# Ethernet.net
KiCad netlist of a schematic drawn in Altium Designer
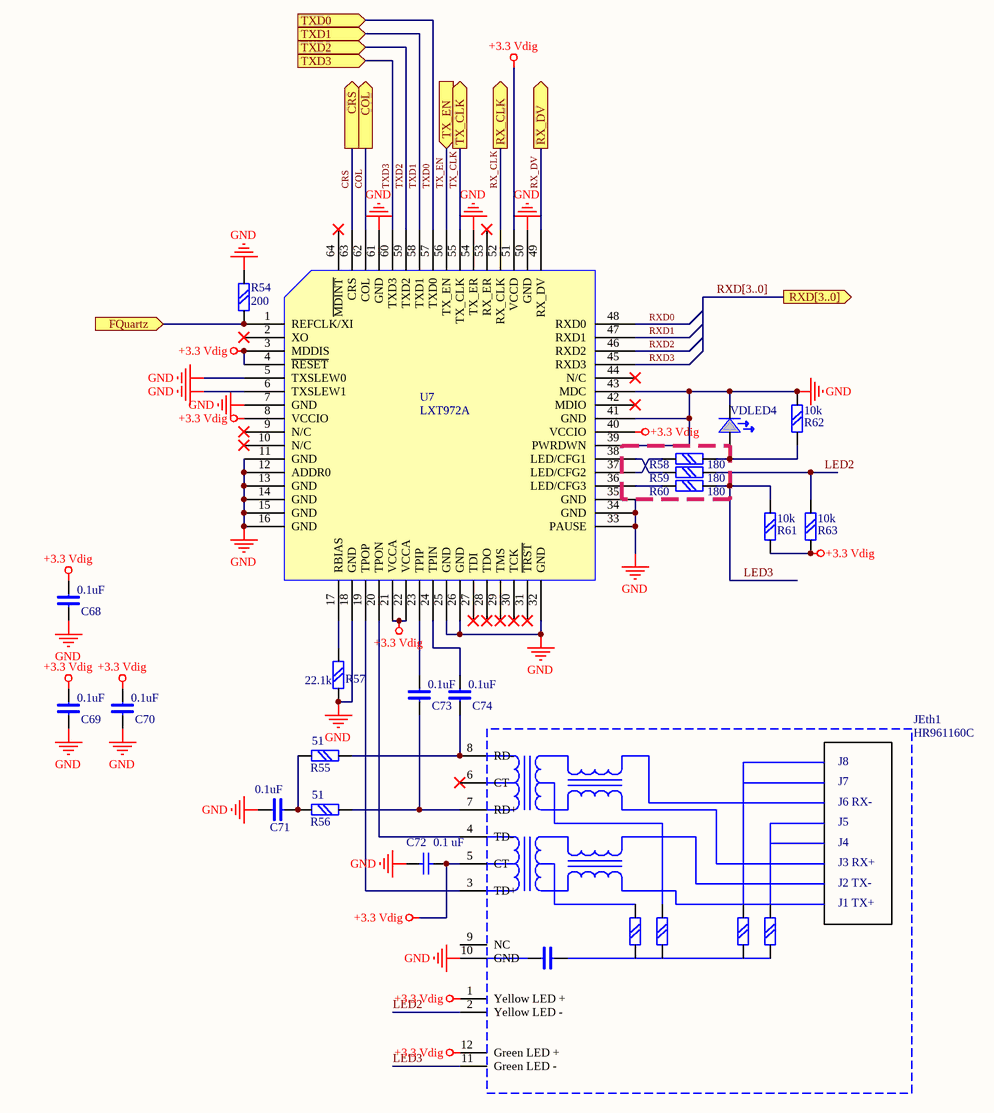
[diagram p0: Ethernet.SchDoc]

(export (version "E")
  (design (tool "Eeschema 10.0.6"))
  (components
    (comp (ref "C68") (value "0.1uF") (footprint "chip0603") (libsource (lib "vDevice") (part "C")))
    (comp (ref "C69") (value "0.1uF") (footprint "chip0603") (libsource (lib "vDevice") (part "C")))
    (comp (ref "C70") (value "0.1uF") (footprint "chip0603") (libsource (lib "vDevice") (part "C")))
    (comp (ref "C71") (value "0.1uF") (footprint "chip0603") (libsource (lib "vDevice") (part "C")))
    (comp (ref "C72")
      (value "0.1 uF")
      (footprint "chip0603")
      (description "Capacitor")
      (fields (field (name "Comment") "0.1uF") (field (name "PUBLISHER") "Altium Limited"))
      (libsource (lib "vDevice") (part "Cap"))
    )
    (comp (ref "C73") (value "0.1uF") (footprint "chip0603") (libsource (lib "vDevice") (part "C")))
    (comp (ref "C74") (value "0.1uF") (footprint "chip0603") (libsource (lib "vDevice") (part "C")))
    (comp (ref "JEth1")
      (value "HR961160C")
      (footprint "HR961160C")
      (libsource (lib "Backup of Mylib") (part "HR961160C"))
    )
    (comp (ref "R54") (value "200") (footprint "chip0603") (libsource (lib "vDevice") (part "R")))
    (comp (ref "R55") (value "51") (footprint "chip0603") (libsource (lib "vDevice") (part "R")))
    (comp (ref "R56") (value "51") (footprint "chip0603") (libsource (lib "vDevice") (part "R")))
    (comp (ref "R57") (value "22.1k") (footprint "chip0603") (libsource (lib "vDevice") (part "R")))
    (comp (ref "R58") (value "180") (footprint "chip0603") (libsource (lib "vDevice") (part "R")))
    (comp (ref "R59") (value "180") (footprint "chip0603") (libsource (lib "vDevice") (part "R")))
    (comp (ref "R60") (value "180") (footprint "chip0603") (libsource (lib "vDevice") (part "R")))
    (comp (ref "R61") (value "10k") (footprint "chip0603") (libsource (lib "vDevice") (part "R")))
    (comp (ref "R62") (value "10k") (footprint "chip0603") (libsource (lib "vDevice") (part "R")))
    (comp (ref "R63") (value "10k") (footprint "chip0603") (libsource (lib "vDevice") (part "R")))
    (comp (ref "U7")
      (value "LXT972A")
      (footprint "TQFP64")
      (libsource (lib "Backup of Mylib") (part "LXT972A"))
    )
    (comp (ref "VDLED4") (value "LED") (footprint "LED0805") (libsource (lib "*") (part "AL307")))
  )
  (nets
    (net (code "1") (name "+3.3 Vdig") (class "Default")
      (node (ref "C68") (pin "2") (pinfunction "2_2") (pintype "passive"))
      (node (ref "C69") (pin "2") (pinfunction "2_2") (pintype "passive"))
      (node (ref "C70") (pin "2") (pinfunction "2_2") (pintype "passive"))
      (node (ref "C72") (pin "2") (pinfunction "2_2") (pintype "passive"))
      (node (ref "JEth1") (pin "1") (pinfunction "Yellow_LED_+_1") (pintype "passive"))
      (node (ref "JEth1") (pin "12") (pinfunction "Green_LED_+_12") (pintype "passive"))
      (node (ref "JEth1") (pin "5") (pinfunction "CT_5") (pintype "passive"))
      (node (ref "R61") (pin "1") (pinfunction "1_1") (pintype "passive"))
      (node (ref "R63") (pin "1") (pinfunction "1_1") (pintype "passive"))
      (node (ref "U7") (pin "21") (pinfunction "VCCA_21") (pintype "passive"))
      (node (ref "U7") (pin "22") (pinfunction "VCCA_22") (pintype "passive"))
      (node (ref "U7") (pin "3") (pinfunction "MDDIS_3") (pintype "passive"))
      (node (ref "U7") (pin "4") (pinfunction "RESET_4") (pintype "passive"))
      (node (ref "U7") (pin "40") (pinfunction "VCCIO_40") (pintype "passive"))
      (node (ref "U7") (pin "51") (pinfunction "VCCD_51") (pintype "passive"))
      (node (ref "U7") (pin "8") (pinfunction "VCCIO_8") (pintype "passive"))
    )
    (net (code "2") (name "/COL") (class "Default")
      (node (ref "U7") (pin "62") (pinfunction "COL_62") (pintype "passive"))
    )
    (net (code "3") (name "/CRS") (class "Default")
      (node (ref "U7") (pin "63") (pinfunction "CRS_63") (pintype "passive"))
    )
    (net (code "4") (name "/FQuartz") (class "Default")
      (node (ref "R54") (pin "1") (pinfunction "1_1") (pintype "passive"))
      (node (ref "U7") (pin "1") (pinfunction "REFCLK/XI_1") (pintype "passive"))
    )
    (net (code "5") (name "/LED2") (class "Default")
      (node (ref "JEth1") (pin "2") (pinfunction "Yellow_LED_-_2") (pintype "passive"))
      (node (ref "R59") (pin "2") (pinfunction "2_2") (pintype "passive"))
      (node (ref "R63") (pin "2") (pinfunction "2_2") (pintype "passive"))
    )
    (net (code "6") (name "/LED3") (class "Default")
      (node (ref "JEth1") (pin "11") (pinfunction "Green_LED_-_11") (pintype "passive"))
      (node (ref "R60") (pin "2") (pinfunction "2_2") (pintype "passive"))
      (node (ref "R61") (pin "2") (pinfunction "2_2") (pintype "passive"))
    )
    (net (code "7") (name "/RXD0") (class "Default")
      (node (ref "U7") (pin "48") (pinfunction "RXD0_48") (pintype "passive"))
    )
    (net (code "8") (name "/RXD1") (class "Default")
      (node (ref "U7") (pin "47") (pinfunction "RXD1_47") (pintype "passive"))
    )
    (net (code "9") (name "/RXD2") (class "Default")
      (node (ref "U7") (pin "46") (pinfunction "RXD2_46") (pintype "passive"))
    )
    (net (code "10") (name "/RXD3") (class "Default")
      (node (ref "U7") (pin "45") (pinfunction "RXD3_45") (pintype "passive"))
    )
    (net (code "12") (name "/RX_CLK") (class "Default")
      (node (ref "U7") (pin "52") (pinfunction "RX_CLK_52") (pintype "passive"))
    )
    (net (code "13") (name "/RX_DV") (class "Default")
      (node (ref "U7") (pin "49") (pinfunction "RX_DV_49") (pintype "passive"))
    )
    (net (code "14") (name "/TXD0") (class "Default")
      (node (ref "U7") (pin "57") (pinfunction "TXD0_57") (pintype "passive"))
    )
    (net (code "15") (name "/TXD1") (class "Default")
      (node (ref "U7") (pin "58") (pinfunction "TXD1_58") (pintype "passive"))
    )
    (net (code "16") (name "/TXD2") (class "Default")
      (node (ref "U7") (pin "59") (pinfunction "TXD2_59") (pintype "passive"))
    )
    (net (code "17") (name "/TXD3") (class "Default")
      (node (ref "U7") (pin "60") (pinfunction "TXD3_60") (pintype "passive"))
    )
    (net (code "18") (name "/TX_CLK") (class "Default")
      (node (ref "U7") (pin "55") (pinfunction "TX_CLK_55") (pintype "passive"))
    )
    (net (code "19") (name "/TX_EN") (class "Default")
      (node (ref "U7") (pin "56") (pinfunction "TX_EN_56") (pintype "passive"))
    )
    (net (code "20") (name "GND") (class "Default")
      (node (ref "C68") (pin "1") (pinfunction "1_1") (pintype "passive"))
      (node (ref "C69") (pin "1") (pinfunction "1_1") (pintype "passive"))
      (node (ref "C70") (pin "1") (pinfunction "1_1") (pintype "passive"))
      (node (ref "C71") (pin "2") (pinfunction "2_2") (pintype "passive"))
      (node (ref "C72") (pin "1") (pinfunction "1_1") (pintype "passive"))
      (node (ref "JEth1") (pin "10") (pinfunction "GND_10") (pintype "power_in"))
      (node (ref "R54") (pin "2") (pinfunction "2_2") (pintype "passive"))
      (node (ref "R57") (pin "2") (pinfunction "2_2") (pintype "passive"))
      (node (ref "R62") (pin "2") (pinfunction "2_2") (pintype "passive"))
      (node (ref "U7") (pin "11") (pinfunction "GND_11") (pintype "passive"))
      (node (ref "U7") (pin "12") (pinfunction "ADDR0_12") (pintype "passive"))
      (node (ref "U7") (pin "13") (pinfunction "GND_13") (pintype "passive"))
      (node (ref "U7") (pin "14") (pinfunction "GND_14") (pintype "passive"))
      (node (ref "U7") (pin "15") (pinfunction "GND_15") (pintype "passive"))
      (node (ref "U7") (pin "16") (pinfunction "GND_16") (pintype "passive"))
      (node (ref "U7") (pin "18") (pinfunction "GND_18") (pintype "passive"))
      (node (ref "U7") (pin "25") (pinfunction "GND_25") (pintype "passive"))
      (node (ref "U7") (pin "26") (pinfunction "GND_26") (pintype "passive"))
      (node (ref "U7") (pin "32") (pinfunction "GND_32") (pintype "passive"))
      (node (ref "U7") (pin "33") (pinfunction "PAUSE_33") (pintype "passive"))
      (node (ref "U7") (pin "34") (pinfunction "GND_34") (pintype "passive"))
      (node (ref "U7") (pin "35") (pinfunction "GND_35") (pintype "passive"))
      (node (ref "U7") (pin "39") (pinfunction "PWRDWN_39") (pintype "passive"))
      (node (ref "U7") (pin "41") (pinfunction "GND_41") (pintype "passive"))
      (node (ref "U7") (pin "43") (pinfunction "MDC_43") (pintype "passive"))
      (node (ref "U7") (pin "5") (pinfunction "TXSLEW0_5") (pintype "passive"))
      (node (ref "U7") (pin "50") (pinfunction "GND_50") (pintype "passive"))
      (node (ref "U7") (pin "54") (pinfunction "TX_ER_54") (pintype "passive"))
      (node (ref "U7") (pin "6") (pinfunction "TXSLEW1_6") (pintype "passive"))
      (node (ref "U7") (pin "61") (pinfunction "GND_61") (pintype "passive"))
      (node (ref "U7") (pin "7") (pinfunction "GND_7") (pintype "passive"))
      (node (ref "VDLED4") (pin "CATH") (pinfunction "CATH_CATH") (pintype "passive"))
    )
    (net (code "21") (name "Net-(C71-Pad1)") (class "Default")
      (node (ref "C71") (pin "1") (pinfunction "1_1") (pintype "passive"))
      (node (ref "R55") (pin "1") (pinfunction "1_1") (pintype "passive"))
      (node (ref "R56") (pin "2") (pinfunction "2_2") (pintype "passive"))
    )
    (net (code "22") (name "Net-(JEth1-RD+)") (class "Default")
      (node (ref "C73") (pin "1") (pinfunction "1_1") (pintype "passive"))
      (node (ref "JEth1") (pin "7") (pinfunction "RD+_7") (pintype "passive"))
      (node (ref "R56") (pin "1") (pinfunction "1_1") (pintype "passive"))
    )
    (net (code "23") (name "Net-(JEth1-RD-)") (class "Default")
      (node (ref "C74") (pin "1") (pinfunction "1_1") (pintype "passive"))
      (node (ref "JEth1") (pin "8") (pinfunction "RD-_8") (pintype "passive"))
      (node (ref "R55") (pin "2") (pinfunction "2_2") (pintype "passive"))
    )
    (net (code "24") (name "Net-(JEth1-TD+)") (class "Default")
      (node (ref "JEth1") (pin "3") (pinfunction "TD+_3") (pintype "passive"))
      (node (ref "U7") (pin "19") (pinfunction "TPOP_19") (pintype "passive"))
    )
    (net (code "25") (name "Net-(JEth1-TD-)") (class "Default")
      (node (ref "JEth1") (pin "4") (pinfunction "TD-_4") (pintype "passive"))
      (node (ref "U7") (pin "20") (pinfunction "TPON_20") (pintype "passive"))
    )
    (net (code "26") (name "Net-(R58-Pad2)") (class "Default")
      (node (ref "R58") (pin "2") (pinfunction "2_2") (pintype "passive"))
      (node (ref "R62") (pin "1") (pinfunction "1_1") (pintype "passive"))
      (node (ref "VDLED4") (pin "ANOD") (pinfunction "ANOD_ANOD") (pintype "passive"))
    )
    (net (code "27") (name "Net-(U7-LED{slash}CFG1)") (class "Default")
      (node (ref "R59") (pin "1") (pinfunction "1_1") (pintype "passive"))
      (node (ref "U7") (pin "38") (pinfunction "LED/CFG1_38") (pintype "passive"))
    )
    (net (code "28") (name "Net-(U7-LED{slash}CFG2)") (class "Default")
      (node (ref "R58") (pin "1") (pinfunction "1_1") (pintype "passive"))
      (node (ref "U7") (pin "37") (pinfunction "LED/CFG2_37") (pintype "passive"))
    )
    (net (code "29") (name "Net-(U7-LED{slash}CFG3)") (class "Default")
      (node (ref "R60") (pin "1") (pinfunction "1_1") (pintype "passive"))
      (node (ref "U7") (pin "36") (pinfunction "LED/CFG3_36") (pintype "passive"))
    )
    (net (code "30") (name "Net-(U7-RBIAS)") (class "Default")
      (node (ref "R57") (pin "1") (pinfunction "1_1") (pintype "passive"))
      (node (ref "U7") (pin "17") (pinfunction "RBIAS_17") (pintype "passive"))
    )
    (net (code "31") (name "Net-(U7-TPIN)") (class "Default")
      (node (ref "C74") (pin "2") (pinfunction "2_2") (pintype "passive"))
      (node (ref "U7") (pin "24") (pinfunction "TPIN_24") (pintype "passive"))
    )
    (net (code "32") (name "Net-(U7-TPIP)") (class "Default")
      (node (ref "C73") (pin "2") (pinfunction "2_2") (pintype "passive"))
      (node (ref "U7") (pin "23") (pinfunction "TPIP_23") (pintype "passive"))
    )
    (net (code "33") (name "unconnected-(JEth1-CT-Pad6)") (class "Default")
      (node (ref "JEth1") (pin "6") (pinfunction "CT_6") (pintype "passive+no_connect"))
    )
    (net (code "34") (name "unconnected-(JEth1-NC-Pad9)") (class "Default")
      (node (ref "JEth1") (pin "9") (pinfunction "NC_9") (pintype "passive"))
    )
    (net (code "35") (name "unconnected-(JEth1-Pad1)") (class "Default")
      (node (ref "JEth1") (pin "1") (pinfunction "1_1") (pintype "passive"))
    )
    (net (code "36") (name "unconnected-(JEth1-Pad1)_1") (class "Default")
      (node (ref "JEth1") (pin "1") (pinfunction "1_1") (pintype "passive"))
    )
    (net (code "37") (name "unconnected-(JEth1-Pad1)_2") (class "Default")
      (node (ref "JEth1") (pin "1") (pinfunction "1_1") (pintype "passive"))
    )
    (net (code "38") (name "unconnected-(JEth1-Pad1)_3") (class "Default")
      (node (ref "JEth1") (pin "1") (pinfunction "1_1") (pintype "passive"))
    )
    (net (code "39") (name "unconnected-(JEth1-Pad1)_4") (class "Default")
      (node (ref "JEth1") (pin "1") (pinfunction "1_1") (pintype "passive"))
    )
    (net (code "40") (name "unconnected-(JEth1-Pad2)") (class "Default")
      (node (ref "JEth1") (pin "2") (pinfunction "2_2") (pintype "passive"))
    )
    (net (code "41") (name "unconnected-(JEth1-Pad2)_1") (class "Default")
      (node (ref "JEth1") (pin "2") (pinfunction "2_2") (pintype "passive"))
    )
    (net (code "42") (name "unconnected-(JEth1-Pad2)_2") (class "Default")
      (node (ref "JEth1") (pin "2") (pinfunction "2_2") (pintype "passive"))
    )
    (net (code "43") (name "unconnected-(JEth1-Pad2)_3") (class "Default")
      (node (ref "JEth1") (pin "2") (pinfunction "2_2") (pintype "passive"))
    )
    (net (code "44") (name "unconnected-(JEth1-Pad2)_4") (class "Default")
      (node (ref "JEth1") (pin "2") (pinfunction "2_2") (pintype "passive"))
    )
    (net (code "45") (name "unconnected-(U7-MDINT-Pad64)") (class "Default")
      (node (ref "U7") (pin "64") (pinfunction "MDINT_64") (pintype "passive+no_connect"))
    )
    (net (code "46") (name "unconnected-(U7-MDIO-Pad42)") (class "Default")
      (node (ref "U7") (pin "42") (pinfunction "MDIO_42") (pintype "passive+no_connect"))
    )
    (net (code "47") (name "unconnected-(U7-N{slash}C-Pad9)") (class "Default")
      (node (ref "U7") (pin "9") (pinfunction "N/C_9") (pintype "passive+no_connect"))
    )
    (net (code "48") (name "unconnected-(U7-N{slash}C-Pad10)") (class "Default")
      (node (ref "U7") (pin "10") (pinfunction "N/C_10") (pintype "passive+no_connect"))
    )
    (net (code "49") (name "unconnected-(U7-N{slash}C-Pad44)") (class "Default")
      (node (ref "U7") (pin "44") (pinfunction "N/C_44") (pintype "passive+no_connect"))
    )
    (net (code "50") (name "unconnected-(U7-RX_ER-Pad53)") (class "Default")
      (node (ref "U7") (pin "53") (pinfunction "RX_ER_53") (pintype "passive+no_connect"))
    )
    (net (code "51") (name "unconnected-(U7-TCK-Pad30)") (class "Default")
      (node (ref "U7") (pin "30") (pinfunction "TCK_30") (pintype "passive+no_connect"))
    )
    (net (code "52") (name "unconnected-(U7-TDI-Pad27)") (class "Default")
      (node (ref "U7") (pin "27") (pinfunction "TDI_27") (pintype "passive+no_connect"))
    )
    (net (code "53") (name "unconnected-(U7-TDO-Pad28)") (class "Default")
      (node (ref "U7") (pin "28") (pinfunction "TDO_28") (pintype "passive+no_connect"))
    )
    (net (code "54") (name "unconnected-(U7-TMS-Pad29)") (class "Default")
      (node (ref "U7") (pin "29") (pinfunction "TMS_29") (pintype "passive+no_connect"))
    )
    (net (code "55") (name "unconnected-(U7-TRST-Pad31)") (class "Default")
      (node (ref "U7") (pin "31") (pinfunction "TRST_31") (pintype "passive+no_connect"))
    )
    (net (code "56") (name "unconnected-(U7-XO-Pad2)") (class "Default")
      (node (ref "U7") (pin "2") (pinfunction "XO_2") (pintype "passive+no_connect"))
    )
  )
)
